# Seven_Seg_Control_-_Schematic.net
KiCad netlist of a schematic drawn in EAGLE
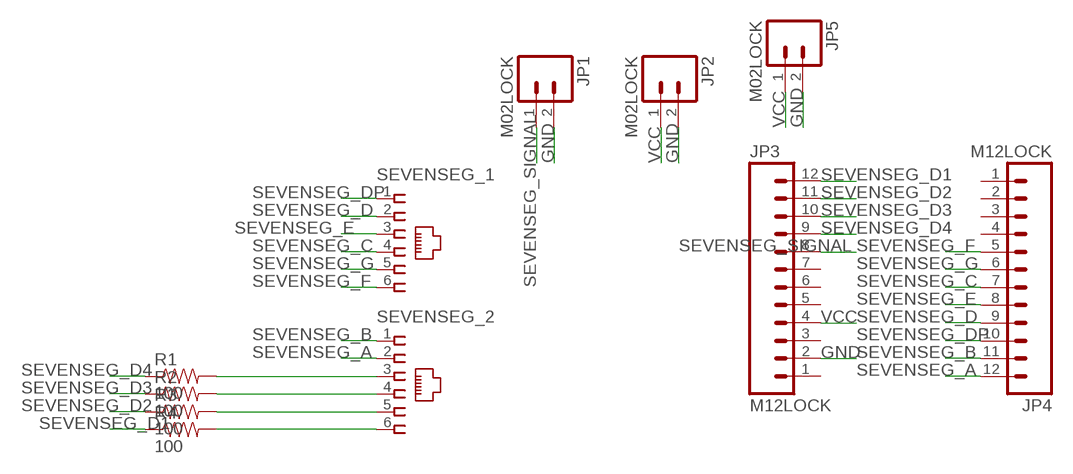
[diagram p0: schematic, sheet 1]

(export (version "E")
  (design (tool "Eeschema 10.0.6"))
  (components
    (comp (ref "JP1")
      (value "M02LOCK")
      (footprint "eagle-import:1X02_LOCK")
      (libsource (lib "eagle-import") (part "M02LOCK"))
    )
    (comp (ref "JP2")
      (value "M02LOCK")
      (footprint "eagle-import:1X02_LOCK")
      (libsource (lib "eagle-import") (part "M02LOCK"))
    )
    (comp (ref "JP3")
      (value "M12LOCK")
      (footprint "eagle-import:1X12_LOCK")
      (libsource (lib "eagle-import") (part "M12LOCK"))
    )
    (comp (ref "JP4")
      (value "M12LOCK")
      (footprint "eagle-import:1X12_LOCK")
      (libsource (lib "eagle-import") (part "M12LOCK"))
    )
    (comp (ref "JP5")
      (value "M02LOCK")
      (footprint "eagle-import:1X02_LOCK")
      (libsource (lib "eagle-import") (part "M02LOCK"))
    )
    (comp (ref "R1")
      (value "100")
      (footprint "eagle-import:0603-RES")
      (libsource (lib "eagle-import") (part "RESISTOR0603"))
    )
    (comp (ref "R2")
      (value "100")
      (footprint "eagle-import:0603-RES")
      (libsource (lib "eagle-import") (part "RESISTOR0603"))
    )
    (comp (ref "R3")
      (value "100")
      (footprint "eagle-import:0603-RES")
      (libsource (lib "eagle-import") (part "RESISTOR0603"))
    )
    (comp (ref "R4")
      (value "100")
      (footprint "eagle-import:0603-RES")
      (libsource (lib "eagle-import") (part "RESISTOR0603"))
    )
    (comp (ref "SEVENSEG_1")
      (value "555165-1")
      (footprint "eagle-import:555165-1")
      (libsource (lib "eagle-import") (part "555165-1"))
    )
    (comp (ref "SEVENSEG_2")
      (value "555165-1")
      (footprint "eagle-import:555165-1")
      (libsource (lib "eagle-import") (part "555165-1"))
    )
  )
  (nets
    (net (code "1") (name "/GND") (class "Default")
      (node (ref "JP1") (pin "2") (pinfunction "2_2") (pintype "passive"))
      (node (ref "JP2") (pin "2") (pinfunction "2_2") (pintype "passive"))
      (node (ref "JP3") (pin "2") (pinfunction "2_2") (pintype "passive"))
      (node (ref "JP5") (pin "2") (pinfunction "2_2") (pintype "passive"))
    )
    (net (code "2") (name "/SEVENSEG_A") (class "Default")
      (node (ref "JP4") (pin "12") (pinfunction "12_12") (pintype "passive"))
      (node (ref "SEVENSEG_2") (pin "2") (pinfunction "2_2") (pintype "passive"))
    )
    (net (code "3") (name "/SEVENSEG_B") (class "Default")
      (node (ref "JP4") (pin "11") (pinfunction "11_11") (pintype "passive"))
      (node (ref "SEVENSEG_2") (pin "1") (pinfunction "1_1") (pintype "passive"))
    )
    (net (code "4") (name "/SEVENSEG_C") (class "Default")
      (node (ref "JP4") (pin "7") (pinfunction "7_7") (pintype "passive"))
      (node (ref "SEVENSEG_1") (pin "4") (pinfunction "4_4") (pintype "passive"))
    )
    (net (code "5") (name "/SEVENSEG_D") (class "Default")
      (node (ref "JP4") (pin "9") (pinfunction "9_9") (pintype "passive"))
      (node (ref "SEVENSEG_1") (pin "2") (pinfunction "2_2") (pintype "passive"))
    )
    (net (code "6") (name "/SEVENSEG_D1") (class "Default")
      (node (ref "JP3") (pin "12") (pinfunction "12_12") (pintype "passive"))
      (node (ref "R4") (pin "1") (pinfunction "1_1") (pintype "passive"))
    )
    (net (code "7") (name "/SEVENSEG_D2") (class "Default")
      (node (ref "JP3") (pin "11") (pinfunction "11_11") (pintype "passive"))
      (node (ref "R3") (pin "1") (pinfunction "1_1") (pintype "passive"))
    )
    (net (code "8") (name "/SEVENSEG_D3") (class "Default")
      (node (ref "JP3") (pin "10") (pinfunction "10_10") (pintype "passive"))
      (node (ref "R2") (pin "1") (pinfunction "1_1") (pintype "passive"))
    )
    (net (code "9") (name "/SEVENSEG_D4") (class "Default")
      (node (ref "JP3") (pin "9") (pinfunction "9_9") (pintype "passive"))
      (node (ref "R1") (pin "1") (pinfunction "1_1") (pintype "passive"))
    )
    (net (code "10") (name "/SEVENSEG_DP") (class "Default")
      (node (ref "JP4") (pin "10") (pinfunction "10_10") (pintype "passive"))
      (node (ref "SEVENSEG_1") (pin "1") (pinfunction "1_1") (pintype "passive"))
    )
    (net (code "11") (name "/SEVENSEG_E") (class "Default")
      (node (ref "JP4") (pin "8") (pinfunction "8_8") (pintype "passive"))
      (node (ref "SEVENSEG_1") (pin "3") (pinfunction "3_3") (pintype "passive"))
    )
    (net (code "12") (name "/SEVENSEG_F") (class "Default")
      (node (ref "JP4") (pin "5") (pinfunction "5_5") (pintype "passive"))
      (node (ref "SEVENSEG_1") (pin "6") (pinfunction "6_6") (pintype "passive"))
    )
    (net (code "13") (name "/SEVENSEG_G") (class "Default")
      (node (ref "JP4") (pin "6") (pinfunction "6_6") (pintype "passive"))
      (node (ref "SEVENSEG_1") (pin "5") (pinfunction "5_5") (pintype "passive"))
    )
    (net (code "14") (name "/SEVENSEG_SIGNAL") (class "Default")
      (node (ref "JP1") (pin "1") (pinfunction "1_1") (pintype "passive"))
      (node (ref "JP3") (pin "8") (pinfunction "8_8") (pintype "passive"))
    )
    (net (code "15") (name "/VCC") (class "Default")
      (node (ref "JP2") (pin "1") (pinfunction "1_1") (pintype "passive"))
      (node (ref "JP3") (pin "4") (pinfunction "4_4") (pintype "passive"))
      (node (ref "JP5") (pin "1") (pinfunction "1_1") (pintype "passive"))
    )
    (net (code "16") (name "Net-(R1-Pad2)") (class "Default")
      (node (ref "R1") (pin "2") (pinfunction "2_2") (pintype "passive"))
      (node (ref "SEVENSEG_2") (pin "3") (pinfunction "3_3") (pintype "passive"))
    )
    (net (code "17") (name "Net-(R2-Pad2)") (class "Default")
      (node (ref "R2") (pin "2") (pinfunction "2_2") (pintype "passive"))
      (node (ref "SEVENSEG_2") (pin "4") (pinfunction "4_4") (pintype "passive"))
    )
    (net (code "18") (name "Net-(R3-Pad2)") (class "Default")
      (node (ref "R3") (pin "2") (pinfunction "2_2") (pintype "passive"))
      (node (ref "SEVENSEG_2") (pin "5") (pinfunction "5_5") (pintype "passive"))
    )
    (net (code "19") (name "Net-(R4-Pad2)") (class "Default")
      (node (ref "R4") (pin "2") (pinfunction "2_2") (pintype "passive"))
      (node (ref "SEVENSEG_2") (pin "6") (pinfunction "6_6") (pintype "passive"))
    )
    (net (code "20") (name "unconnected-(JP3-Pad1)") (class "Default")
      (node (ref "JP3") (pin "1") (pinfunction "1_1") (pintype "passive"))
    )
    (net (code "21") (name "unconnected-(JP3-Pad3)") (class "Default")
      (node (ref "JP3") (pin "3") (pinfunction "3_3") (pintype "passive"))
    )
    (net (code "22") (name "unconnected-(JP3-Pad5)") (class "Default")
      (node (ref "JP3") (pin "5") (pinfunction "5_5") (pintype "passive"))
    )
    (net (code "23") (name "unconnected-(JP3-Pad6)") (class "Default")
      (node (ref "JP3") (pin "6") (pinfunction "6_6") (pintype "passive"))
    )
    (net (code "24") (name "unconnected-(JP3-Pad7)") (class "Default")
      (node (ref "JP3") (pin "7") (pinfunction "7_7") (pintype "passive"))
    )
    (net (code "25") (name "unconnected-(JP4-Pad1)") (class "Default")
      (node (ref "JP4") (pin "1") (pinfunction "1_1") (pintype "passive"))
    )
    (net (code "26") (name "unconnected-(JP4-Pad2)") (class "Default")
      (node (ref "JP4") (pin "2") (pinfunction "2_2") (pintype "passive"))
    )
    (net (code "27") (name "unconnected-(JP4-Pad3)") (class "Default")
      (node (ref "JP4") (pin "3") (pinfunction "3_3") (pintype "passive"))
    )
    (net (code "28") (name "unconnected-(JP4-Pad4)") (class "Default")
      (node (ref "JP4") (pin "4") (pinfunction "4_4") (pintype "passive"))
    )
  )
)
